# amplis.net
KiCad netlist of a schematic drawn in Altium Designer
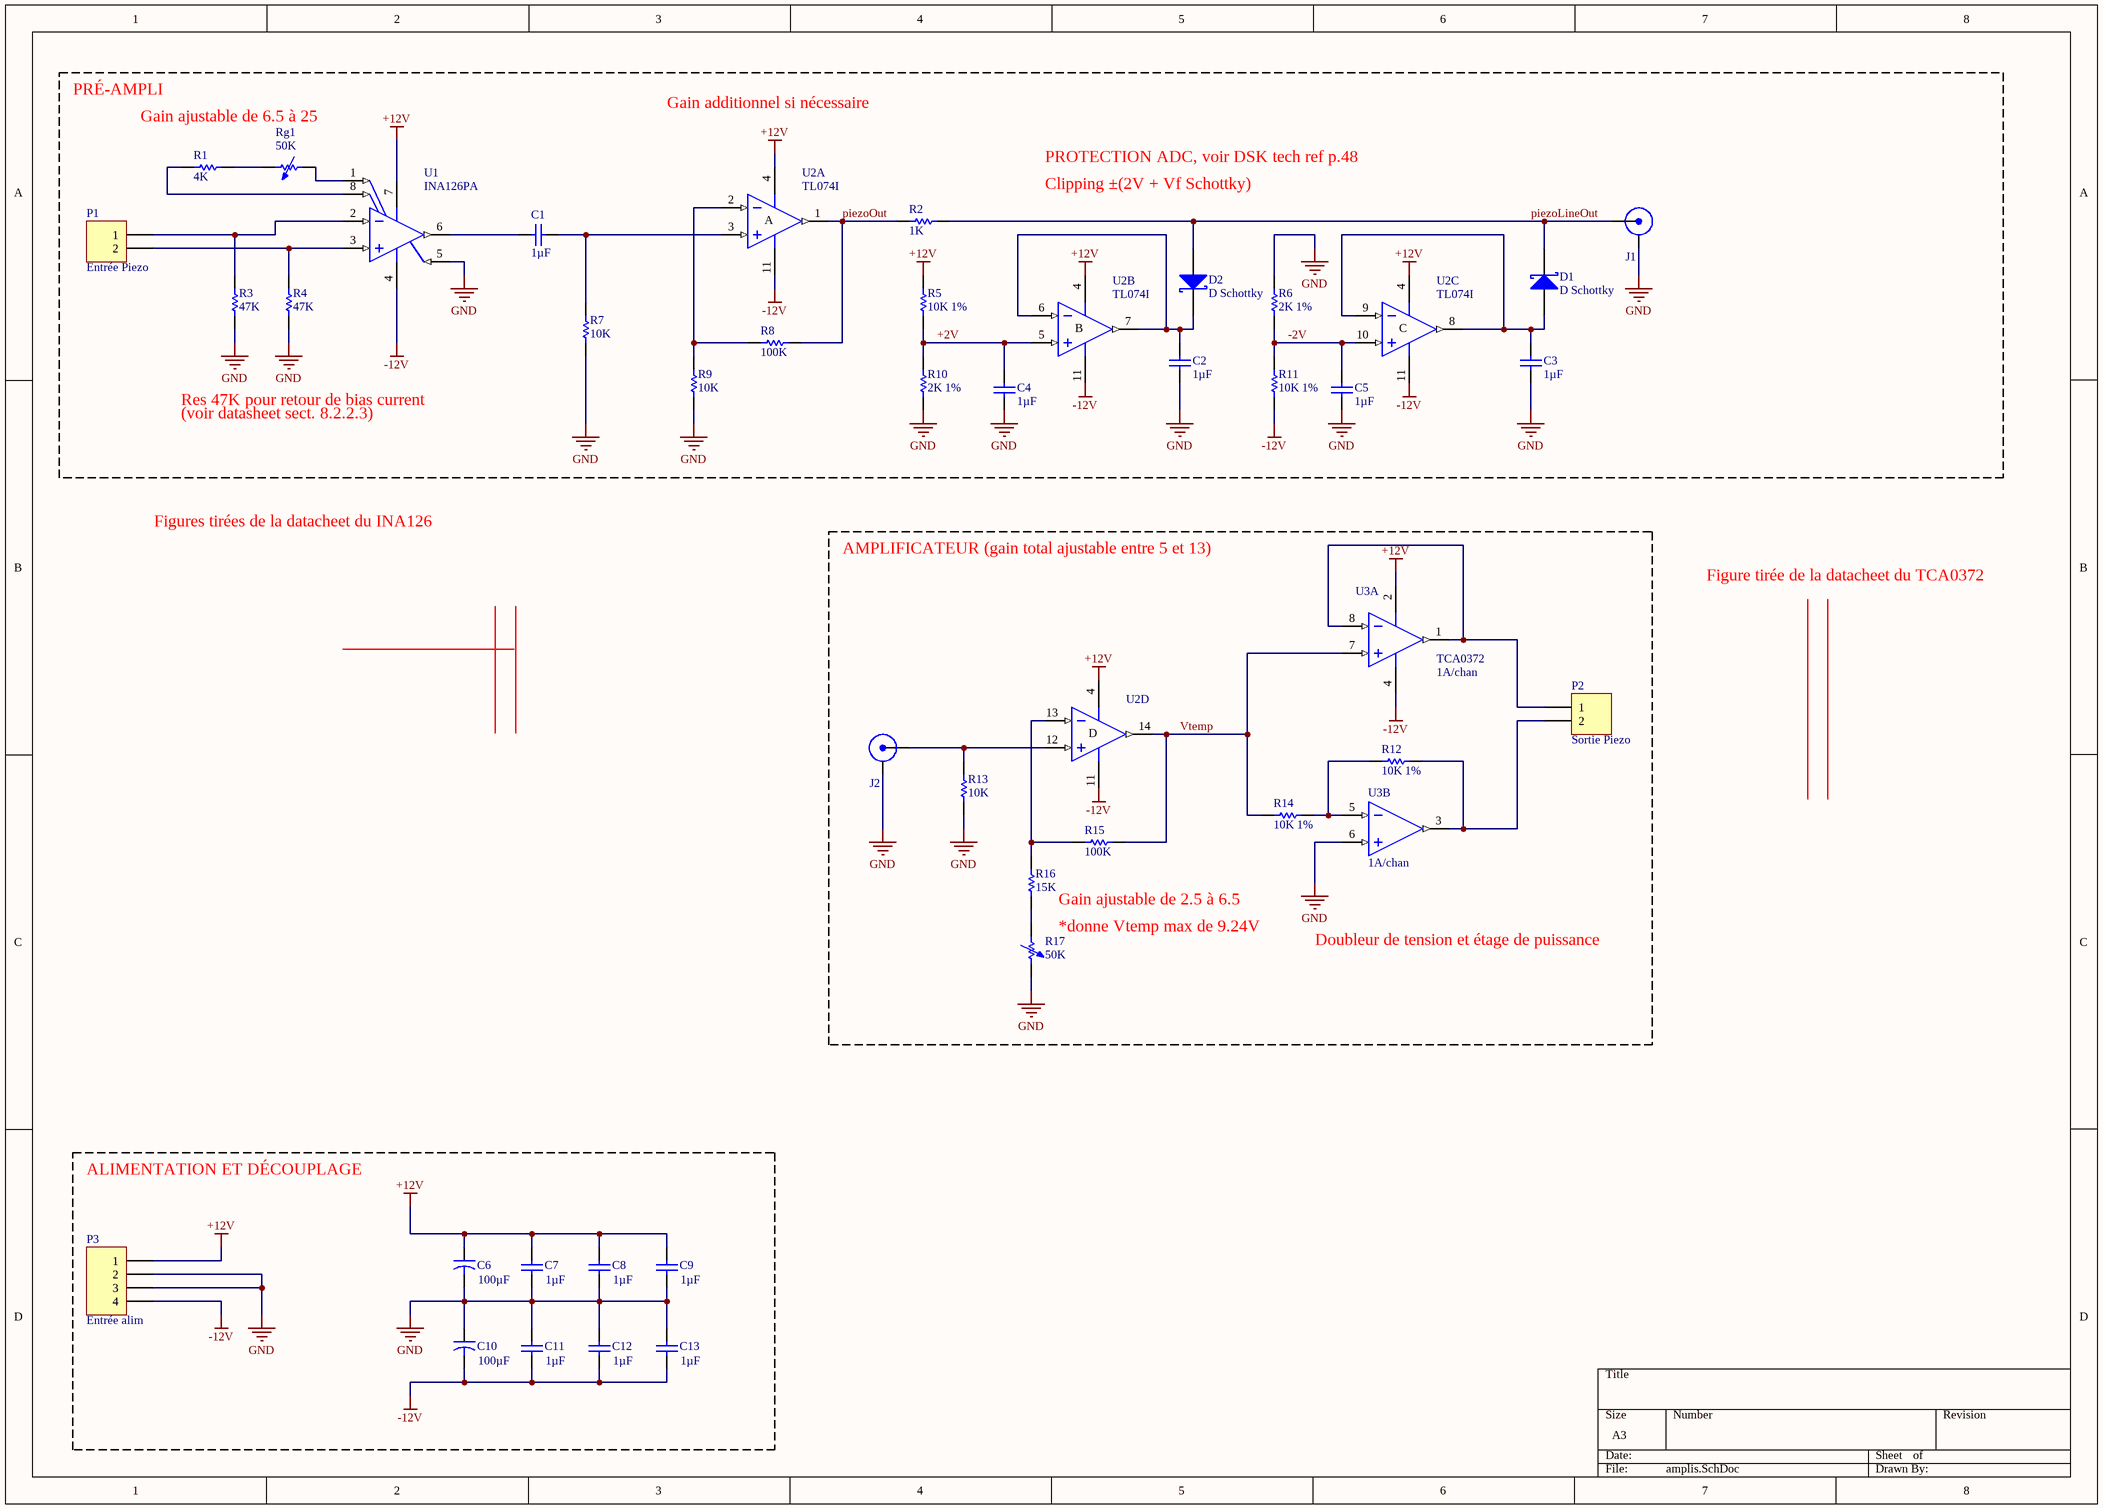
[diagram p0: amplis.SchDoc]

(export (version "E")
  (design (tool "Eeschema 10.0.6"))
  (components
    (comp (ref "C1")
      (value "1µF")
      (footprint "RAD-0.3")
      (description "Capacitor")
      (fields (field (name "Comment") "Cap") (field (name "PUBLISHER") "Altium Limited"))
      (libsource (lib "Miscellaneous Devices") (part "Cap"))
    )
    (comp (ref "C2")
      (value "1µF")
      (footprint "RAD-0.3")
      (description "Capacitor")
      (fields (field (name "Comment") "Cap") (field (name "PUBLISHER") "Altium Limited"))
      (libsource (lib "Miscellaneous Devices") (part "Cap"))
    )
    (comp (ref "C3")
      (value "1µF")
      (footprint "RAD-0.3")
      (description "Capacitor")
      (fields (field (name "Comment") "Cap") (field (name "PUBLISHER") "Altium Limited"))
      (libsource (lib "Miscellaneous Devices") (part "Cap"))
    )
    (comp (ref "C4")
      (value "1µF")
      (footprint "RAD-0.3")
      (description "Capacitor")
      (fields (field (name "Comment") "Cap") (field (name "PUBLISHER") "Altium Limited"))
      (libsource (lib "Miscellaneous Devices") (part "Cap"))
    )
    (comp (ref "C5")
      (value "1µF")
      (footprint "RAD-0.3")
      (description "Capacitor")
      (fields (field (name "Comment") "Cap") (field (name "PUBLISHER") "Altium Limited"))
      (libsource (lib "Miscellaneous Devices") (part "Cap"))
    )
    (comp (ref "C6")
      (value "100µF")
      (footprint "CAPR5-4X5")
      (description "Capacitor")
      (fields (field (name "Comment") "Cap2") (field (name "PUBLISHER") "Altium Limited"))
      (libsource (lib "Miscellaneous Devices") (part "Cap2"))
    )
    (comp (ref "C7")
      (value "1µF")
      (footprint "RAD-0.3")
      (description "Capacitor")
      (fields (field (name "Comment") "Cap") (field (name "PUBLISHER") "Altium Limited"))
      (libsource (lib "Miscellaneous Devices") (part "Cap"))
    )
    (comp (ref "C8")
      (value "1µF")
      (footprint "RAD-0.3")
      (description "Capacitor")
      (fields (field (name "Comment") "Cap") (field (name "PUBLISHER") "Altium Limited"))
      (libsource (lib "Miscellaneous Devices") (part "Cap"))
    )
    (comp (ref "C9")
      (value "1µF")
      (footprint "RAD-0.3")
      (description "Capacitor")
      (fields (field (name "Comment") "Cap") (field (name "PUBLISHER") "Altium Limited"))
      (libsource (lib "Miscellaneous Devices") (part "Cap"))
    )
    (comp (ref "C10")
      (value "100µF")
      (footprint "CAPR5-4X5")
      (description "Capacitor")
      (fields (field (name "Comment") "Cap2") (field (name "PUBLISHER") "Altium Limited"))
      (libsource (lib "Miscellaneous Devices") (part "Cap2"))
    )
    (comp (ref "C11")
      (value "1µF")
      (footprint "RAD-0.3")
      (description "Capacitor")
      (fields (field (name "Comment") "Cap") (field (name "PUBLISHER") "Altium Limited"))
      (libsource (lib "Miscellaneous Devices") (part "Cap"))
    )
    (comp (ref "C12")
      (value "1µF")
      (footprint "RAD-0.3")
      (description "Capacitor")
      (fields (field (name "Comment") "Cap") (field (name "PUBLISHER") "Altium Limited"))
      (libsource (lib "Miscellaneous Devices") (part "Cap"))
    )
    (comp (ref "C13")
      (value "1µF")
      (footprint "RAD-0.3")
      (description "Capacitor")
      (fields (field (name "Comment") "Cap") (field (name "PUBLISHER") "Altium Limited"))
      (libsource (lib "Miscellaneous Devices") (part "Cap"))
    )
    (comp (ref "D1")
      (value "D Schottky")
      (footprint "SMB")
      (description "Schottky Diode")
      (fields (field (name "PUBLISHER") "Altium Limited"))
      (libsource (lib "Miscellaneous Devices") (part "D Schottky"))
    )
    (comp (ref "D2")
      (value "D Schottky")
      (footprint "SMB")
      (description "Schottky Diode")
      (fields (field (name "PUBLISHER") "Altium Limited"))
      (libsource (lib "Miscellaneous Devices") (part "D Schottky"))
    )
    (comp (ref "J1") (value "BNC") (footprint "BNC_Vertical") (libsource (lib "S3_projet") (part "BNC")))
    (comp (ref "J2") (value "BNC") (footprint "BNC_Vertical") (libsource (lib "S3_projet") (part "BNC")))
    (comp (ref "P1")
      (value "Entrée Piezo")
      (footprint "HDR1X2")
      (description "Header, 2-Pin")
      (fields (field (name "PUBLISHER") "Altium Limited"))
      (libsource (lib "Miscellaneous Connectors") (part "Header 2"))
    )
    (comp (ref "P2")
      (value "Sortie Piezo")
      (footprint "HDR1X2")
      (description "Header, 2-Pin")
      (fields (field (name "PUBLISHER") "Altium Limited"))
      (libsource (lib "") (part "Header 2_1"))
    )
    (comp (ref "P3")
      (value "Entrée alim")
      (footprint "HDR1X4")
      (description "Header, 4-Pin")
      (fields (field (name "PUBLISHER") "Altium Limited"))
      (libsource (lib "Miscellaneous Connectors") (part "Header 4"))
    )
    (comp (ref "R1")
      (value "4K")
      (footprint "AXIAL-0.3")
      (description "Resistor")
      (fields (field (name "Comment") "Res1") (field (name "PUBLISHER") "Altium Limited"))
      (libsource (lib "Miscellaneous Devices") (part "Res1"))
    )
    (comp (ref "R2")
      (value "1K")
      (footprint "AXIAL-0.3")
      (description "Resistor")
      (fields (field (name "Comment") "Res1") (field (name "PUBLISHER") "Altium Limited"))
      (libsource (lib "Miscellaneous Devices") (part "Res1"))
    )
    (comp (ref "R3")
      (value "47K")
      (footprint "AXIAL-0.3")
      (description "Resistor")
      (fields (field (name "Comment") "Res1") (field (name "PUBLISHER") "Altium Limited"))
      (libsource (lib "Miscellaneous Devices") (part "Res1"))
    )
    (comp (ref "R4")
      (value "47K")
      (footprint "AXIAL-0.3")
      (description "Resistor")
      (fields (field (name "Comment") "Res1") (field (name "PUBLISHER") "Altium Limited"))
      (libsource (lib "Miscellaneous Devices") (part "Res1"))
    )
    (comp (ref "R5")
      (value "10K 1%")
      (footprint "AXIAL-0.3")
      (description "Resistor")
      (fields (field (name "Comment") "Res1") (field (name "PUBLISHER") "Altium Limited"))
      (libsource (lib "Miscellaneous Devices") (part "Res1"))
    )
    (comp (ref "R6")
      (value "2K 1%")
      (footprint "AXIAL-0.3")
      (description "Resistor")
      (fields (field (name "Comment") "Res1") (field (name "PUBLISHER") "Altium Limited"))
      (libsource (lib "Miscellaneous Devices") (part "Res1"))
    )
    (comp (ref "R7")
      (value "10K")
      (footprint "AXIAL-0.3")
      (description "Resistor")
      (fields (field (name "Comment") "Res1") (field (name "PUBLISHER") "Altium Limited"))
      (libsource (lib "Miscellaneous Devices") (part "Res1"))
    )
    (comp (ref "R8")
      (value "100K")
      (footprint "AXIAL-0.3")
      (description "Resistor")
      (fields (field (name "Comment") "Res1") (field (name "PUBLISHER") "Altium Limited"))
      (libsource (lib "Miscellaneous Devices") (part "Res1"))
    )
    (comp (ref "R9")
      (value "10K")
      (footprint "AXIAL-0.3")
      (description "Resistor")
      (fields (field (name "Comment") "Res1") (field (name "PUBLISHER") "Altium Limited"))
      (libsource (lib "Miscellaneous Devices") (part "Res1"))
    )
    (comp (ref "R10")
      (value "2K 1%")
      (footprint "AXIAL-0.3")
      (description "Resistor")
      (fields (field (name "Comment") "Res1") (field (name "PUBLISHER") "Altium Limited"))
      (libsource (lib "Miscellaneous Devices") (part "Res1"))
    )
    (comp (ref "R11")
      (value "10K 1%")
      (footprint "AXIAL-0.3")
      (description "Resistor")
      (fields (field (name "Comment") "Res1") (field (name "PUBLISHER") "Altium Limited"))
      (libsource (lib "Miscellaneous Devices") (part "Res1"))
    )
    (comp (ref "R12")
      (value "10K 1%")
      (footprint "AXIAL-0.3")
      (description "Resistor")
      (fields (field (name "Comment") "Res1") (field (name "PUBLISHER") "Altium Limited"))
      (libsource (lib "Miscellaneous Devices") (part "Res1"))
    )
    (comp (ref "R13")
      (value "10K")
      (footprint "AXIAL-0.3")
      (description "Resistor")
      (fields (field (name "Comment") "Res1") (field (name "PUBLISHER") "Altium Limited"))
      (libsource (lib "Miscellaneous Devices") (part "Res1"))
    )
    (comp (ref "R14")
      (value "10K 1%")
      (footprint "AXIAL-0.3")
      (description "Resistor")
      (fields (field (name "Comment") "Res1") (field (name "PUBLISHER") "Altium Limited"))
      (libsource (lib "Miscellaneous Devices") (part "Res1"))
    )
    (comp (ref "R15")
      (value "100K")
      (footprint "AXIAL-0.3")
      (description "Resistor")
      (fields (field (name "Comment") "Res1") (field (name "PUBLISHER") "Altium Limited"))
      (libsource (lib "Miscellaneous Devices") (part "Res1"))
    )
    (comp (ref "R16")
      (value "15K")
      (footprint "AXIAL-0.3")
      (description "Resistor")
      (fields (field (name "Comment") "Res1") (field (name "PUBLISHER") "Altium Limited"))
      (libsource (lib "Miscellaneous Devices") (part "Res1"))
    )
    (comp (ref "R17")
      (value "50K")
      (footprint "AXIAL-0.7")
      (description "Variable Resistor")
      (fields (field (name "Comment") "Res Adj1") (field (name "PUBLISHER") "Altium Limited"))
      (libsource (lib "Miscellaneous Devices") (part "Res Adj1"))
    )
    (comp (ref "Rg1")
      (value "50K")
      (footprint "AXIAL-0.7")
      (description "Variable Resistor")
      (fields (field (name "Comment") "Res Adj1") (field (name "PUBLISHER") "Altium Limited"))
      (libsource (lib "Miscellaneous Devices") (part "Res Adj1"))
    )
    (comp (ref "U1")
      (value "INA126PA")
      (footprint "TI-P8")
      (fields (field (name "MANUFACTURER") "Texas Instruments"))
      (libsource (lib "TI Amplifiers and Linear Instrumentation Amplifier") (part "INA126PA"))
    )
    (comp (ref "U2")
      (value "TL074I")
      (footprint "SOIC-14")
      (description "Low-Noise J-FET Quad Operational Amplifier")
      (fields (field (name "PUBLISHER") "Altium Limited"))
      (libsource (lib "S3_projet") (part "TL074I"))
    )
    (comp (ref "U3")
      (value "1A/chan")
      (fields (field (name "MODEL") "TCA0372"))
      (libsource (lib "lib_projet") (part "TCA0372_case626"))
    )
  )
  (nets
    (net (code "1") (name "+12V") (class "Default")
      (node (ref "C6") (pin "1") (pinfunction "1_1") (pintype "passive"))
      (node (ref "C7") (pin "2") (pinfunction "2_2") (pintype "passive"))
      (node (ref "C8") (pin "2") (pinfunction "2_2") (pintype "passive"))
      (node (ref "C9") (pin "2") (pinfunction "2_2") (pintype "passive"))
      (node (ref "P3") (pin "1") (pinfunction "1_1") (pintype "passive"))
      (node (ref "R5") (pin "1") (pinfunction "1_1") (pintype "passive"))
      (node (ref "U1") (pin "7") (pinfunction "V+_7") (pintype "power_in"))
      (node (ref "U2") (pin "4") (pinfunction "V+_4") (pintype "power_in"))
      (node (ref "U3") (pin "2") (pinfunction "V+_2") (pintype "power_in"))
    )
    (net (code "2") (name "-12V") (class "Default")
      (node (ref "C10") (pin "2") (pinfunction "2_2") (pintype "passive"))
      (node (ref "C11") (pin "1") (pinfunction "1_1") (pintype "passive"))
      (node (ref "C12") (pin "1") (pinfunction "1_1") (pintype "passive"))
      (node (ref "C13") (pin "1") (pinfunction "1_1") (pintype "passive"))
      (node (ref "P3") (pin "4") (pinfunction "4_4") (pintype "passive"))
      (node (ref "R11") (pin "2") (pinfunction "2_2") (pintype "passive"))
      (node (ref "U1") (pin "4") (pinfunction "V-_4") (pintype "power_in"))
      (node (ref "U2") (pin "11") (pinfunction "V-_11") (pintype "power_in"))
      (node (ref "U3") (pin "4") (pinfunction "V-_4") (pintype "power_in"))
    )
    (net (code "3") (name "/+2V") (class "Default")
      (node (ref "C4") (pin "1") (pinfunction "1_1") (pintype "passive"))
      (node (ref "R10") (pin "1") (pinfunction "1_1") (pintype "passive"))
      (node (ref "R5") (pin "2") (pinfunction "2_2") (pintype "passive"))
      (node (ref "U2") (pin "5") (pinfunction "IN+_5") (pintype "input"))
    )
    (net (code "4") (name "/-2V") (class "Default")
      (node (ref "C5") (pin "1") (pinfunction "1_1") (pintype "passive"))
      (node (ref "R11") (pin "1") (pinfunction "1_1") (pintype "passive"))
      (node (ref "R6") (pin "2") (pinfunction "2_2") (pintype "passive"))
      (node (ref "U2") (pin "10") (pinfunction "IN+_10") (pintype "input"))
    )
    (net (code "5") (name "/Vtemp") (class "Default")
      (node (ref "R14") (pin "1") (pinfunction "1_1") (pintype "passive"))
      (node (ref "R15") (pin "1") (pinfunction "1_1") (pintype "passive"))
      (node (ref "U2") (pin "14") (pinfunction "OUT_14") (pintype "output"))
      (node (ref "U3") (pin "7") (pinfunction "VIN+_7") (pintype "input"))
    )
    (net (code "6") (name "/piezoLineOut") (class "Default")
      (node (ref "D1") (pin "2") (pinfunction "K_2") (pintype "passive"))
      (node (ref "D2") (pin "1") (pinfunction "A_1") (pintype "passive"))
      (node (ref "J1") (pin "1") (pinfunction "Sig_1") (pintype "passive"))
      (node (ref "R2") (pin "1") (pinfunction "1_1") (pintype "passive"))
    )
    (net (code "7") (name "/piezoOut") (class "Default")
      (node (ref "R2") (pin "2") (pinfunction "2_2") (pintype "passive"))
      (node (ref "R8") (pin "1") (pinfunction "1_1") (pintype "passive"))
      (node (ref "U2") (pin "1") (pinfunction "OUT_1") (pintype "output"))
    )
    (net (code "8") (name "GND") (class "Default")
      (node (ref "C10") (pin "1") (pinfunction "1_1") (pintype "passive"))
      (node (ref "C11") (pin "2") (pinfunction "2_2") (pintype "passive"))
      (node (ref "C12") (pin "2") (pinfunction "2_2") (pintype "passive"))
      (node (ref "C13") (pin "2") (pinfunction "2_2") (pintype "passive"))
      (node (ref "C2") (pin "2") (pinfunction "2_2") (pintype "passive"))
      (node (ref "C3") (pin "2") (pinfunction "2_2") (pintype "passive"))
      (node (ref "C4") (pin "2") (pinfunction "2_2") (pintype "passive"))
      (node (ref "C5") (pin "2") (pinfunction "2_2") (pintype "passive"))
      (node (ref "C6") (pin "2") (pinfunction "2_2") (pintype "passive"))
      (node (ref "C7") (pin "1") (pinfunction "1_1") (pintype "passive"))
      (node (ref "C8") (pin "1") (pinfunction "1_1") (pintype "passive"))
      (node (ref "C9") (pin "1") (pinfunction "1_1") (pintype "passive"))
      (node (ref "J1") (pin "2") (pinfunction "Gnd_2") (pintype "passive"))
      (node (ref "J2") (pin "2") (pinfunction "Gnd_2") (pintype "passive"))
      (node (ref "P3") (pin "2") (pinfunction "2_2") (pintype "passive"))
      (node (ref "P3") (pin "3") (pinfunction "3_3") (pintype "passive"))
      (node (ref "R10") (pin "2") (pinfunction "2_2") (pintype "passive"))
      (node (ref "R13") (pin "2") (pinfunction "2_2") (pintype "passive"))
      (node (ref "R17") (pin "2") (pinfunction "2_2") (pintype "passive"))
      (node (ref "R3") (pin "1") (pinfunction "1_1") (pintype "passive"))
      (node (ref "R4") (pin "1") (pinfunction "1_1") (pintype "passive"))
      (node (ref "R6") (pin "1") (pinfunction "1_1") (pintype "passive"))
      (node (ref "R7") (pin "2") (pinfunction "2_2") (pintype "passive"))
      (node (ref "R9") (pin "2") (pinfunction "2_2") (pintype "passive"))
      (node (ref "U1") (pin "5") (pinfunction "REF_5") (pintype "input"))
      (node (ref "U3") (pin "6") (pinfunction "VIN+_6") (pintype "input"))
    )
    (net (code "9") (name "Net-(D1-A)") (class "Default")
      (node (ref "C3") (pin "1") (pinfunction "1_1") (pintype "passive"))
      (node (ref "D1") (pin "1") (pinfunction "A_1") (pintype "passive"))
      (node (ref "U2") (pin "8") (pinfunction "OUT_8") (pintype "output"))
      (node (ref "U2") (pin "9") (pinfunction "IN-_9") (pintype "input"))
    )
    (net (code "10") (name "Net-(D2-K)") (class "Default")
      (node (ref "C2") (pin "1") (pinfunction "1_1") (pintype "passive"))
      (node (ref "D2") (pin "2") (pinfunction "K_2") (pintype "passive"))
      (node (ref "U2") (pin "6") (pinfunction "IN-_6") (pintype "input"))
      (node (ref "U2") (pin "7") (pinfunction "OUT_7") (pintype "output"))
    )
    (net (code "11") (name "Net-(J2-Sig)") (class "Default")
      (node (ref "J2") (pin "1") (pinfunction "Sig_1") (pintype "passive"))
      (node (ref "R13") (pin "1") (pinfunction "1_1") (pintype "passive"))
      (node (ref "U2") (pin "12") (pinfunction "IN+_12") (pintype "input"))
    )
    (net (code "12") (name "Net-(R1-Pad1)") (class "Default")
      (node (ref "R1") (pin "1") (pinfunction "1_1") (pintype "passive"))
      (node (ref "Rg1") (pin "2") (pinfunction "2_2") (pintype "passive"))
    )
    (net (code "13") (name "Net-(R1-Pad2)") (class "Default")
      (node (ref "R1") (pin "2") (pinfunction "2_2") (pintype "passive"))
      (node (ref "U1") (pin "8") (pinfunction "RG_8") (pintype "input"))
    )
    (net (code "14") (name "Net-(R16-Pad2)") (class "Default")
      (node (ref "R16") (pin "2") (pinfunction "2_2") (pintype "passive"))
      (node (ref "R17") (pin "1") (pinfunction "1_1") (pintype "passive"))
    )
    (net (code "15") (name "Net-(Rg1-Pad1)") (class "Default")
      (node (ref "Rg1") (pin "1") (pinfunction "1_1") (pintype "passive"))
      (node (ref "U1") (pin "1") (pinfunction "RG_1") (pintype "input"))
    )
    (net (code "16") (name "Net-(U1-VIN+)") (class "Default")
      (node (ref "P1") (pin "2") (pinfunction "2_2") (pintype "passive"))
      (node (ref "R4") (pin "2") (pinfunction "2_2") (pintype "passive"))
      (node (ref "U1") (pin "3") (pinfunction "VIN+_3") (pintype "input"))
    )
    (net (code "17") (name "Net-(U1-VIN-)") (class "Default")
      (node (ref "P1") (pin "1") (pinfunction "1_1") (pintype "passive"))
      (node (ref "R3") (pin "2") (pinfunction "2_2") (pintype "passive"))
      (node (ref "U1") (pin "2") (pinfunction "VIN-_2") (pintype "input"))
    )
    (net (code "18") (name "Net-(U1-VO)") (class "Default")
      (node (ref "C1") (pin "2") (pinfunction "2_2") (pintype "passive"))
      (node (ref "U1") (pin "6") (pinfunction "VO_6") (pintype "output"))
    )
    (net (code "19") (name "Net-(U2A-IN+)") (class "Default")
      (node (ref "C1") (pin "1") (pinfunction "1_1") (pintype "passive"))
      (node (ref "R7") (pin "1") (pinfunction "1_1") (pintype "passive"))
      (node (ref "U2") (pin "3") (pinfunction "IN+_3") (pintype "input"))
    )
    (net (code "20") (name "Net-(U2A-IN-)") (class "Default")
      (node (ref "R8") (pin "2") (pinfunction "2_2") (pintype "passive"))
      (node (ref "R9") (pin "1") (pinfunction "1_1") (pintype "passive"))
      (node (ref "U2") (pin "2") (pinfunction "IN-_2") (pintype "input"))
    )
    (net (code "21") (name "Net-(U2D-IN-)") (class "Default")
      (node (ref "R15") (pin "2") (pinfunction "2_2") (pintype "passive"))
      (node (ref "R16") (pin "1") (pinfunction "1_1") (pintype "passive"))
      (node (ref "U2") (pin "13") (pinfunction "IN-_13") (pintype "input"))
    )
    (net (code "22") (name "Net-(U3A-VIN-)") (class "Default")
      (node (ref "P2") (pin "1") (pinfunction "1_1") (pintype "passive"))
      (node (ref "U3") (pin "1") (pinfunction "VOUT_1") (pintype "output"))
      (node (ref "U3") (pin "8") (pinfunction "VIN-_8") (pintype "input"))
    )
    (net (code "23") (name "Net-(U3B-VIN-)") (class "Default")
      (node (ref "R12") (pin "1") (pinfunction "1_1") (pintype "passive"))
      (node (ref "R14") (pin "2") (pinfunction "2_2") (pintype "passive"))
      (node (ref "U3") (pin "5") (pinfunction "VIN-_5") (pintype "input"))
    )
    (net (code "24") (name "Net-(U3B-VOUT)") (class "Default")
      (node (ref "P2") (pin "2") (pinfunction "2_2") (pintype "passive"))
      (node (ref "R12") (pin "2") (pinfunction "2_2") (pintype "passive"))
      (node (ref "U3") (pin "3") (pinfunction "VOUT_3") (pintype "output"))
    )
  )
)
